# H0AR4_Backend.net
KiCad netlist of a schematic drawn in Altium Designer
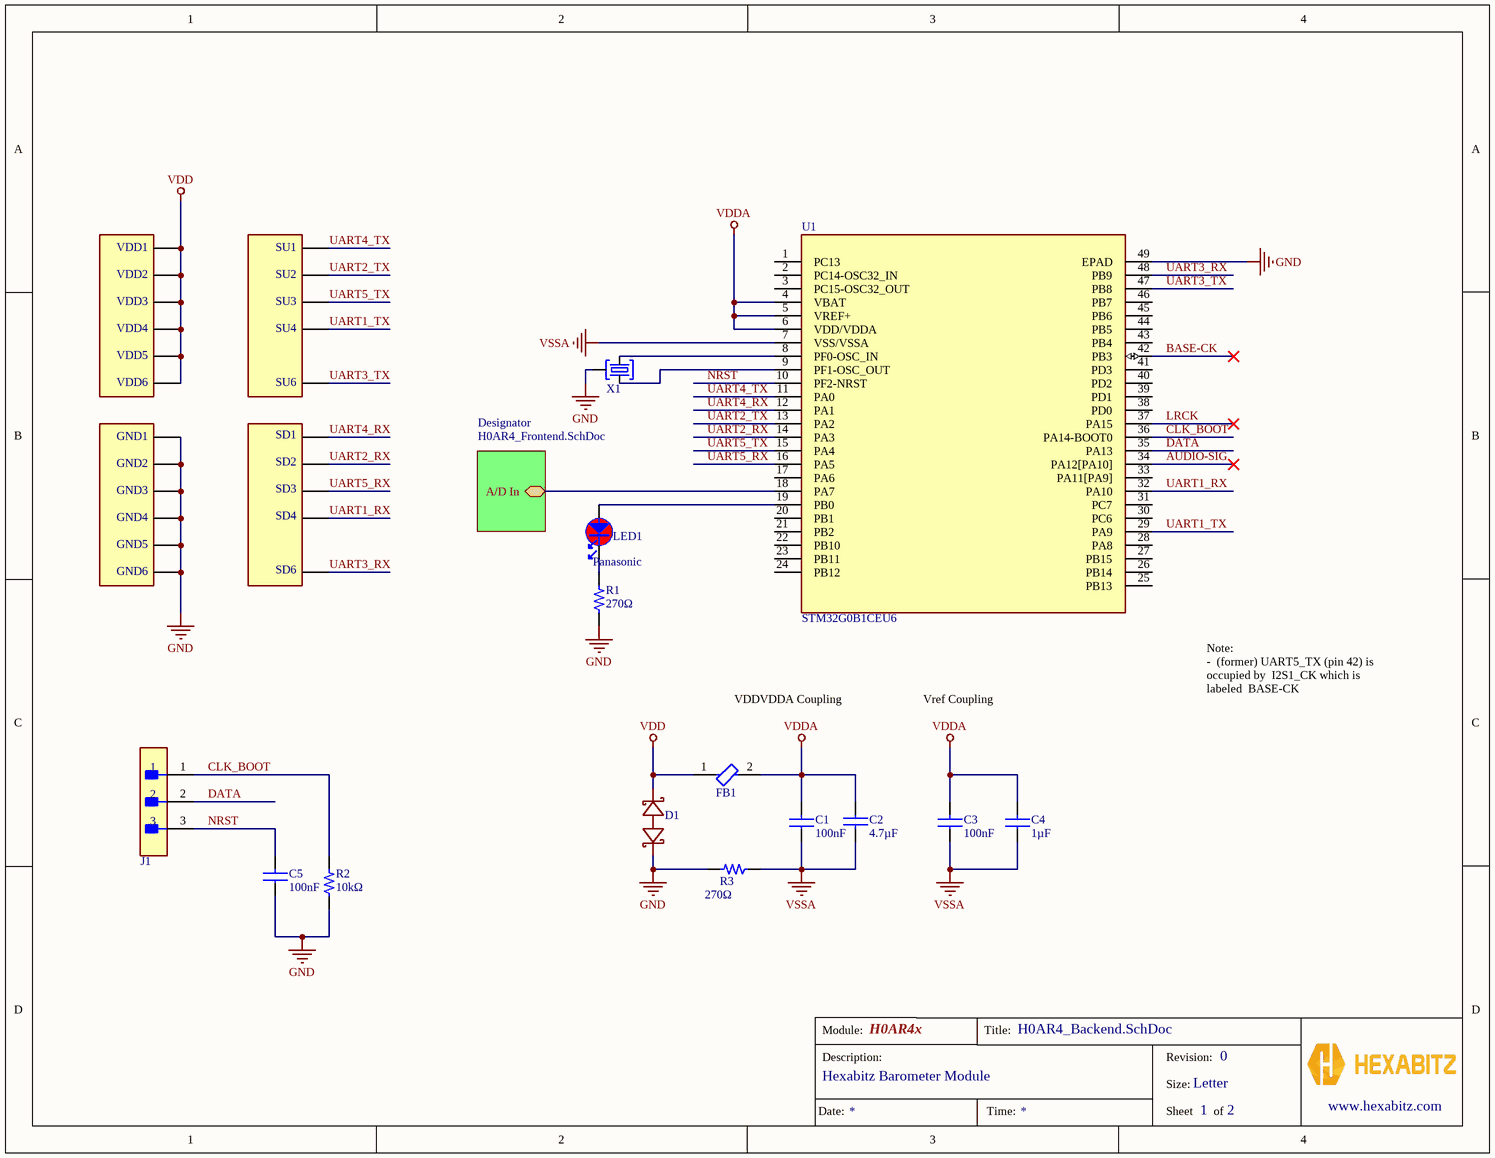
[diagram p0: H0AR4_Backend.SchDoc]

(export (version "E")
  (design (tool "Eeschema 10.0.6"))
  (components
    (comp (ref "C1")
      (value "100nF")
      (footprint "C0603")
      (fields
        (field (name "MANUFACTURER") "Samsung Electro-Mechanics")
        (field (name "MANUFACTURER PART NUMBER") "CL10B104KA8NNNC")
        (field (name "TOLERANCE") "10%")
      )
      (libsource (lib "Hexabitz Altium Library") (part "generic Capacitor"))
    )
    (comp (ref "C2")
      (value "4.7µF")
      (footprint "C0805")
      (fields
        (field (name "MANUFACTURER") "Samsung Electro-Mechanics")
        (field (name "MANUFACTURER PART NUMBER") "CL21X475KAQNNNE")
        (field (name "TOLERANCE") "10%")
      )
      (libsource (lib "Hexabitz Altium Library") (part "generic Capacitor"))
    )
    (comp (ref "C3")
      (value "100nF")
      (footprint "C0603")
      (fields
        (field (name "MANUFACTURER") "Samsung Electro-Mechanics")
        (field (name "MANUFACTURER PART NUMBER") "CL10B104KA8NNNC")
        (field (name "TOLERANCE") "10%")
      )
      (libsource (lib "Hexabitz Altium Library") (part "generic Capacitor"))
    )
    (comp (ref "C4")
      (value "1µF")
      (footprint "C0805")
      (description "Ceramic Capacitor, Ceramic, 16V, 10% +Tol, 10% -Tol, X7R, 15% TC, 1uF, Surface Mount, 0805")
      (fields
        (field (name "MANUFACTURER") "Yageo Group")
        (field (name "MANUFACTURER PART NUMBER") "CC0805KKX7R7BB105")
      )
      (libsource (lib "Hexabitz Altium Library") (part "generic Capacitor"))
    )
    (comp (ref "C5")
      (value "100nF")
      (footprint "C0603")
      (fields
        (field (name "MANUFACTURER") "Samsung Electro-Mechanics")
        (field (name "MANUFACTURER PART NUMBER") "CL10B104KA8NNNC")
        (field (name "TOLERANCE") "10%")
      )
      (libsource (lib "Hexabitz Altium Library") (part "generic Capacitor"))
    )
    (comp (ref "D1")
      (value "CDSOD323-T03SC")
      (footprint "SOD2513X114N")
      (description "A 3V, 350W, bi-directional, standard capacitance, SOD323 pkg TVS Diode ¦ Bourns CDSOD323-T03SC")
      (fields (field (name "MANUFACTURER") "Bourns"))
      (libsource (lib "Hexabitz Altium Library") (part "CDSOD323-T03SC"))
    )
    (comp (ref "FB1")
      (value "MMZ1608Y300B")
      (footprint "FP-MMZ1608-0_8-MFG")
      (description "Ferrite Beads 0603 30ohms 1500mA Signal Line AEC-Q200")
      (fields
        (field (name "MANUFACTURER") "TDK")
        (field (name "MANUFACTURER PART NUMBER") "MMZ1608Y300BTD25")
      )
      (libsource (lib "Hexabitz Altium Library") (part "MMZ1608Y300B"))
    )
    (comp (ref "GND1")
      (value "HEXABIT_UART_PORT")
      (footprint "HEXABIT_POWER_PORT_D")
      (libsource (lib "hexabitz_connectors.Library") (part "HEXABIT_POWER_PORT_D"))
    )
    (comp (ref "GND2")
      (value "HEXABIT_UART_PORT")
      (footprint "HEXABIT_POWER_PORT_D")
      (libsource (lib "hexabitz_connectors.Library") (part "HEXABIT_POWER_PORT_D"))
    )
    (comp (ref "GND3")
      (value "HEXABIT_UART_PORT")
      (footprint "HEXABIT_POWER_PORT_D")
      (libsource (lib "hexabitz_connectors.Library") (part "HEXABIT_POWER_PORT_D"))
    )
    (comp (ref "GND4")
      (value "HEXABIT_UART_PORT")
      (footprint "HEXABIT_POWER_PORT_D")
      (libsource (lib "hexabitz_connectors.Library") (part "HEXABIT_POWER_PORT_D"))
    )
    (comp (ref "GND5")
      (value "HEXABIT_UART_PORT")
      (footprint "HEXABIT_POWER_PORT_D")
      (libsource (lib "hexabitz_connectors.Library") (part "HEXABIT_POWER_PORT_D"))
    )
    (comp (ref "GND6")
      (value "HEXABIT_UART_PORT")
      (footprint "HEXABIT_POWER_PORT_D")
      (libsource (lib "hexabitz_connectors.Library") (part "HEXABIT_POWER_PORT_D"))
    )
    (comp (ref "J1")
      (value "TSW-103-14-G-S")
      (footprint "FP-TSW-103-14-G-S-MFG")
      (description "CONN HEADER VERT 3POS 2.54MM")
      (fields (field (name "MANUFACTURER") "Samtec"))
      (libsource (lib "Altium Content Vault") (part "cd3439d6ef35ae5d9b27ec4fdd3e828"))
    )
    (comp (ref "LED1")
      (value "VLMS1300-GS08")
      (footprint "FP-6_541-5092_01-4-MFG")
      (description "LED Uni-Color Super Red 639nm 2-Pin Chip 0603(1608Metric) T/R")
      (fields (field (name "MANUFACTURER") "Vishay Semiconductors"))
      (libsource (lib "Hexabitz Altium Library") (part "VLMS1300-GS08"))
    )
    (comp (ref "R1")
      (value "270Ω")
      (footprint "R0603")
      (description "Res Thick Film 0603 270 Ohm 5% 0.1W(1/10W) ±200ppm/C Pad SMD Automotive T/R")
      (fields
        (field (name "MANUFACTURER") "Panasonic")
        (field (name "MANUFACTURER PART NUMBER") "ERJ-3GEYJ271V")
        (field (name "TOLERANCE") "5%")
      )
      (libsource (lib "Hexabitz Altium Library") (part "generic Resistor"))
    )
    (comp (ref "R2")
      (value "10kΩ")
      (footprint "R0603")
      (description "100mW Thick Film Resistors ±100ppm/℃ ±1% 10kΩ 0603 Chip Resistor - Surface Mount ROHS")
      (fields
        (field (name "MANUFACTURER") "Yageo Group")
        (field (name "MANUFACTURER PART NUMBER") "RC0603FR-0710KL")
      )
      (libsource (lib "") (part "generic Resistor_1"))
    )
    (comp (ref "R3")
      (value "270Ω")
      (footprint "R0603")
      (description "Res Thick Film 0603 270 Ohm 5% 0.1W(1/10W) ±200ppm/C Pad SMD Automotive T/R")
      (fields (field (name "MANUFACTURER") "Panasonic") (field (name "Comment") "ERJ3GEYJ271V"))
      (libsource (lib "") (part "generic Resistor_2"))
    )
    (comp (ref "SD1")
      (value "HEXABIT_UART_PORT")
      (footprint "HEXABIT_UART_PORT_D")
      (libsource (lib "hexabitz_connectors.Library") (part "HEXABIT_UART_PORT_D"))
    )
    (comp (ref "SD2")
      (value "HEXABIT_UART_PORT")
      (footprint "HEXABIT_UART_PORT_D")
      (libsource (lib "hexabitz_connectors.Library") (part "HEXABIT_UART_PORT_D"))
    )
    (comp (ref "SD3")
      (value "HEXABIT_UART_PORT")
      (footprint "HEXABIT_UART_PORT_D")
      (libsource (lib "hexabitz_connectors.Library") (part "HEXABIT_UART_PORT_D"))
    )
    (comp (ref "SD4")
      (value "HEXABIT_UART_PORT")
      (footprint "HEXABIT_UART_PORT_D")
      (libsource (lib "hexabitz_connectors.Library") (part "HEXABIT_UART_PORT_D"))
    )
    (comp (ref "SD6")
      (value "HEXABIT_UART_PORT")
      (footprint "HEXABIT_UART_PORT_D")
      (libsource (lib "hexabitz_connectors.Library") (part "HEXABIT_UART_PORT_D"))
    )
    (comp (ref "SU1")
      (value "HEXABIT_UART_PORT")
      (footprint "HEXABIT_UART_PORT_U")
      (libsource (lib "hexabitz_connectors.Library") (part "HEXABIT_UART_PORT_U"))
    )
    (comp (ref "SU2")
      (value "HEXABIT_UART_PORT")
      (footprint "HEXABIT_UART_PORT_U")
      (libsource (lib "hexabitz_connectors.Library") (part "HEXABIT_UART_PORT_U"))
    )
    (comp (ref "SU3")
      (value "HEXABIT_UART_PORT")
      (footprint "HEXABIT_UART_PORT_U")
      (libsource (lib "hexabitz_connectors.Library") (part "HEXABIT_UART_PORT_U"))
    )
    (comp (ref "SU4")
      (value "HEXABIT_UART_PORT")
      (footprint "HEXABIT_UART_PORT_U")
      (libsource (lib "hexabitz_connectors.Library") (part "HEXABIT_UART_PORT_U"))
    )
    (comp (ref "SU6")
      (value "HEXABIT_UART_PORT")
      (footprint "HEXABIT_UART_PORT_U")
      (libsource (lib "hexabitz_connectors.Library") (part "HEXABIT_UART_PORT_U"))
    )
    (comp (ref "U1")
      (value "STM32G0B1CEU6")
      (footprint "QFN50P700X700X65-49N-D")
      (description "MCU 32-bit ARM Cortex M0+ RISC 512KB Flash 1.8V/2.5V/3.3V 48-Pin UFQFPN EP Tray")
      (fields
        (field (name "MANUFACTURER") "STMicroelectronics")
        (field (name "MANUFACTURER PART NUMBER") "STM32G0B1CEU6")
      )
      (libsource (lib "Hexabitz Altium Library") (part "STM32G0B1CEU6"))
    )
    (comp (ref "VDD1")
      (value "HEXABIT_UART_PORT")
      (footprint "HEXABIT_POWER_PORT_U")
      (libsource (lib "hexabitz_connectors.Library") (part "HEXABIT_POWER_PORT_U"))
    )
    (comp (ref "VDD2")
      (value "HEXABIT_UART_PORT")
      (footprint "HEXABIT_POWER_PORT_U")
      (libsource (lib "hexabitz_connectors.Library") (part "HEXABIT_POWER_PORT_U"))
    )
    (comp (ref "VDD3")
      (value "HEXABIT_UART_PORT")
      (footprint "HEXABIT_POWER_PORT_U")
      (libsource (lib "hexabitz_connectors.Library") (part "HEXABIT_POWER_PORT_U"))
    )
    (comp (ref "VDD4")
      (value "HEXABIT_UART_PORT")
      (footprint "HEXABIT_POWER_PORT_U")
      (libsource (lib "hexabitz_connectors.Library") (part "HEXABIT_POWER_PORT_U"))
    )
    (comp (ref "VDD5")
      (value "HEXABIT_UART_PORT")
      (footprint "HEXABIT_POWER_PORT_U")
      (libsource (lib "hexabitz_connectors.Library") (part "HEXABIT_POWER_PORT_U"))
    )
    (comp (ref "VDD6")
      (value "HEXABIT_UART_PORT")
      (footprint "HEXABIT_POWER_PORT_U")
      (libsource (lib "hexabitz_connectors.Library") (part "HEXABIT_POWER_PORT_U"))
    )
    (comp (ref "X1")
      (value "CSTCE8M00G52Z-R0")
      (footprint "XTALL_CSTCE8M00G52")
      (description "Ceramic Resonator 8MHz ±0.5% (Tol) ±0.2% (Stability) 10pF 40Ohm 3-Pin CSMD T/R")
      (fields (field (name "MANUFACTURER") "Murata") (field (name "TOLERANCE") "0.5%"))
      (libsource (lib "Hexabitz Altium Library") (part "CSTCE8M00G52Z-R0"))
    )
  )
  (nets
    (net (code "1") (name "/AUDIO-SIG") (class "Default")
      (node (ref "U1") (pin "34") (pinfunction "PA12[PA10]_34") (pintype "passive+no_connect"))
    )
    (net (code "2") (name "/A{slash}D In") (class "Default")
      (node (ref "U1") (pin "18") (pinfunction "PA7_18") (pintype "passive"))
    )
    (net (code "3") (name "/BASE-CK") (class "Default")
      (node (ref "U1") (pin "42") (pinfunction "PB3_42") (pintype "bidirectional+no_connect"))
    )
    (net (code "4") (name "/CLK_BOOT") (class "Default")
      (node (ref "J1") (pin "1") (pinfunction "1_1") (pintype "passive"))
      (node (ref "R2") (pin "1") (pinfunction "1_1") (pintype "passive"))
      (node (ref "U1") (pin "36") (pinfunction "PA14-BOOT0_36") (pintype "passive"))
    )
    (net (code "5") (name "/DATA") (class "Default")
      (node (ref "J1") (pin "2") (pinfunction "2_2") (pintype "passive"))
      (node (ref "U1") (pin "35") (pinfunction "PA13_35") (pintype "passive"))
    )
    (net (code "6") (name "/LRCK") (class "Default")
      (node (ref "U1") (pin "37") (pinfunction "PA15_37") (pintype "passive+no_connect"))
    )
    (net (code "7") (name "/NRST") (class "Default")
      (node (ref "C5") (pin "2") (pinfunction "2_2") (pintype "passive"))
      (node (ref "J1") (pin "3") (pinfunction "3_3") (pintype "passive"))
      (node (ref "U1") (pin "10") (pinfunction "PF2-NRST_10") (pintype "passive"))
    )
    (net (code "8") (name "/UART1_RX") (class "Default")
      (node (ref "SD4") (pin "UART_D") (pinfunction "UART_D_UART_D") (pintype "passive"))
      (node (ref "U1") (pin "32") (pinfunction "PA10_32") (pintype "passive"))
    )
    (net (code "9") (name "/UART1_TX") (class "Default")
      (node (ref "SU4") (pin "UART_U") (pinfunction "UART_U_UART_U") (pintype "passive"))
      (node (ref "U1") (pin "29") (pinfunction "PA9_29") (pintype "passive"))
    )
    (net (code "10") (name "/UART2_RX") (class "Default")
      (node (ref "SD2") (pin "UART_D") (pinfunction "UART_D_UART_D") (pintype "passive"))
      (node (ref "U1") (pin "14") (pinfunction "PA3_14") (pintype "passive"))
    )
    (net (code "11") (name "/UART2_TX") (class "Default")
      (node (ref "SU2") (pin "UART_U") (pinfunction "UART_U_UART_U") (pintype "passive"))
      (node (ref "U1") (pin "13") (pinfunction "PA2_13") (pintype "passive"))
    )
    (net (code "12") (name "/UART3_RX") (class "Default")
      (node (ref "SD6") (pin "UART_D") (pinfunction "UART_D_UART_D") (pintype "passive"))
      (node (ref "U1") (pin "48") (pinfunction "PB9_48") (pintype "passive"))
    )
    (net (code "13") (name "/UART3_TX") (class "Default")
      (node (ref "SU6") (pin "UART_U") (pinfunction "UART_U_UART_U") (pintype "passive"))
      (node (ref "U1") (pin "47") (pinfunction "PB8_47") (pintype "passive"))
    )
    (net (code "14") (name "/UART4_RX") (class "Default")
      (node (ref "SD1") (pin "UART_D") (pinfunction "UART_D_UART_D") (pintype "passive"))
      (node (ref "U1") (pin "12") (pinfunction "PA1_12") (pintype "passive"))
    )
    (net (code "15") (name "/UART4_TX") (class "Default")
      (node (ref "SU1") (pin "UART_U") (pinfunction "UART_U_UART_U") (pintype "passive"))
      (node (ref "U1") (pin "11") (pinfunction "PA0_11") (pintype "passive"))
    )
    (net (code "16") (name "/UART5_RX") (class "Default")
      (node (ref "SD3") (pin "UART_D") (pinfunction "UART_D_UART_D") (pintype "passive"))
      (node (ref "U1") (pin "16") (pinfunction "PA5_16") (pintype "passive"))
    )
    (net (code "17") (name "/UART5_TX") (class "Default")
      (node (ref "SU3") (pin "UART_U") (pinfunction "UART_U_UART_U") (pintype "passive"))
      (node (ref "U1") (pin "15") (pinfunction "PA4_15") (pintype "passive"))
    )
    (net (code "18") (name "GND") (class "Default")
      (node (ref "C5") (pin "1") (pinfunction "1_1") (pintype "passive"))
      (node (ref "D1") (pin "1") (pinfunction "A_1") (pintype "passive"))
      (node (ref "GND1") (pin "Pwr_D") (pinfunction "Pwr_D_Pwr_D") (pintype "passive"))
      (node (ref "GND2") (pin "Pwr_D") (pinfunction "Pwr_D_Pwr_D") (pintype "passive"))
      (node (ref "GND3") (pin "Pwr_D") (pinfunction "Pwr_D_Pwr_D") (pintype "passive"))
      (node (ref "GND4") (pin "Pwr_D") (pinfunction "Pwr_D_Pwr_D") (pintype "passive"))
      (node (ref "GND5") (pin "Pwr_D") (pinfunction "Pwr_D_Pwr_D") (pintype "passive"))
      (node (ref "GND6") (pin "Pwr_D") (pinfunction "Pwr_D_Pwr_D") (pintype "passive"))
      (node (ref "R1") (pin "1") (pinfunction "1_1") (pintype "passive"))
      (node (ref "R2") (pin "2") (pinfunction "2_2") (pintype "passive"))
      (node (ref "R3") (pin "1") (pinfunction "1_1") (pintype "passive"))
      (node (ref "U1") (pin "49") (pinfunction "EPAD_49") (pintype "passive"))
      (node (ref "X1") (pin "P$2") (pinfunction "2_P$2") (pintype "passive"))
    )
    (net (code "19") (name "Net-(LED1-Pad1)") (class "Default")
      (node (ref "LED1") (pin "1") (pintype "passive"))
      (node (ref "R1") (pin "2") (pinfunction "2_2") (pintype "passive"))
    )
    (net (code "20") (name "Net-(U1-PB0)") (class "Default")
      (node (ref "LED1") (pin "2") (pintype "passive"))
      (node (ref "U1") (pin "19") (pinfunction "PB0_19") (pintype "passive"))
    )
    (net (code "21") (name "Net-(U1-PF0-OSC_IN)") (class "Default")
      (node (ref "U1") (pin "8") (pinfunction "PF0-OSC_IN_8") (pintype "passive"))
      (node (ref "X1") (pin "P$3") (pinfunction "3_P$3") (pintype "passive"))
    )
    (net (code "22") (name "Net-(U1-PF1-OSC_OUT)") (class "Default")
      (node (ref "U1") (pin "9") (pinfunction "PF1-OSC_OUT_9") (pintype "passive"))
      (node (ref "X1") (pin "P$1") (pinfunction "1_P$1") (pintype "passive"))
    )
    (net (code "23") (name "VDD") (class "Default")
      (node (ref "D1") (pin "2") (pinfunction "C_2") (pintype "passive"))
      (node (ref "FB1") (pin "1") (pinfunction "1_1") (pintype "passive"))
      (node (ref "VDD1") (pin "Pwr_U") (pinfunction "Pwr_U_Pwr_U") (pintype "passive"))
      (node (ref "VDD2") (pin "Pwr_U") (pinfunction "Pwr_U_Pwr_U") (pintype "passive"))
      (node (ref "VDD3") (pin "Pwr_U") (pinfunction "Pwr_U_Pwr_U") (pintype "passive"))
      (node (ref "VDD4") (pin "Pwr_U") (pinfunction "Pwr_U_Pwr_U") (pintype "passive"))
      (node (ref "VDD5") (pin "Pwr_U") (pinfunction "Pwr_U_Pwr_U") (pintype "passive"))
      (node (ref "VDD6") (pin "Pwr_U") (pinfunction "Pwr_U_Pwr_U") (pintype "passive"))
    )
    (net (code "24") (name "VDDA") (class "Default")
      (node (ref "C1") (pin "2") (pinfunction "2_2") (pintype "passive"))
      (node (ref "C2") (pin "1") (pinfunction "1_1") (pintype "passive"))
      (node (ref "C3") (pin "2") (pinfunction "2_2") (pintype "passive"))
      (node (ref "C4") (pin "2") (pinfunction "2_2") (pintype "passive"))
      (node (ref "FB1") (pin "2") (pinfunction "2_2") (pintype "passive"))
      (node (ref "U1") (pin "4") (pinfunction "VBAT_4") (pintype "passive"))
      (node (ref "U1") (pin "5") (pinfunction "VREF+_5") (pintype "passive"))
      (node (ref "U1") (pin "6") (pinfunction "VDD/VDDA_6") (pintype "passive"))
    )
    (net (code "25") (name "VSSA") (class "Default")
      (node (ref "C1") (pin "1") (pinfunction "1_1") (pintype "passive"))
      (node (ref "C2") (pin "2") (pinfunction "2_2") (pintype "passive"))
      (node (ref "C3") (pin "1") (pinfunction "1_1") (pintype "passive"))
      (node (ref "C4") (pin "1") (pinfunction "1_1") (pintype "passive"))
      (node (ref "R3") (pin "2") (pinfunction "2_2") (pintype "passive"))
      (node (ref "U1") (pin "7") (pinfunction "VSS/VSSA_7") (pintype "passive"))
    )
    (net (code "26") (name "unconnected-(U1-PA6-Pad17)") (class "Default")
      (node (ref "U1") (pin "17") (pinfunction "PA6_17") (pintype "passive"))
    )
    (net (code "27") (name "unconnected-(U1-PA8-Pad28)") (class "Default")
      (node (ref "U1") (pin "28") (pinfunction "PA8_28") (pintype "passive"))
    )
    (net (code "28") (name "unconnected-(U1-PA11[PA9]-Pad33)") (class "Default")
      (node (ref "U1") (pin "33") (pinfunction "PA11[PA9]_33") (pintype "passive"))
    )
    (net (code "29") (name "unconnected-(U1-PB1-Pad20)") (class "Default")
      (node (ref "U1") (pin "20") (pinfunction "PB1_20") (pintype "passive"))
    )
    (net (code "30") (name "unconnected-(U1-PB2-Pad21)") (class "Default")
      (node (ref "U1") (pin "21") (pinfunction "PB2_21") (pintype "passive"))
    )
    (net (code "31") (name "unconnected-(U1-PB4-Pad43)") (class "Default")
      (node (ref "U1") (pin "43") (pinfunction "PB4_43") (pintype "passive"))
    )
    (net (code "32") (name "unconnected-(U1-PB5-Pad44)") (class "Default")
      (node (ref "U1") (pin "44") (pinfunction "PB5_44") (pintype "passive"))
    )
    (net (code "33") (name "unconnected-(U1-PB6-Pad45)") (class "Default")
      (node (ref "U1") (pin "45") (pinfunction "PB6_45") (pintype "passive"))
    )
    (net (code "34") (name "unconnected-(U1-PB7-Pad46)") (class "Default")
      (node (ref "U1") (pin "46") (pinfunction "PB7_46") (pintype "passive"))
    )
    (net (code "35") (name "unconnected-(U1-PB10-Pad22)") (class "Default")
      (node (ref "U1") (pin "22") (pinfunction "PB10_22") (pintype "passive"))
    )
    (net (code "36") (name "unconnected-(U1-PB11-Pad23)") (class "Default")
      (node (ref "U1") (pin "23") (pinfunction "PB11_23") (pintype "passive"))
    )
    (net (code "37") (name "unconnected-(U1-PB12-Pad24)") (class "Default")
      (node (ref "U1") (pin "24") (pinfunction "PB12_24") (pintype "passive"))
    )
    (net (code "38") (name "unconnected-(U1-PB13-Pad25)") (class "Default")
      (node (ref "U1") (pin "25") (pinfunction "PB13_25") (pintype "passive"))
    )
    (net (code "39") (name "unconnected-(U1-PB14-Pad26)") (class "Default")
      (node (ref "U1") (pin "26") (pinfunction "PB14_26") (pintype "passive"))
    )
    (net (code "40") (name "unconnected-(U1-PB15-Pad27)") (class "Default")
      (node (ref "U1") (pin "27") (pinfunction "PB15_27") (pintype "passive"))
    )
    (net (code "41") (name "unconnected-(U1-PC6-Pad30)") (class "Default")
      (node (ref "U1") (pin "30") (pinfunction "PC6_30") (pintype "passive"))
    )
    (net (code "42") (name "unconnected-(U1-PC7-Pad31)") (class "Default")
      (node (ref "U1") (pin "31") (pinfunction "PC7_31") (pintype "passive"))
    )
    (net (code "43") (name "unconnected-(U1-PC13-Pad1)") (class "Default")
      (node (ref "U1") (pin "1") (pinfunction "PC13_1") (pintype "passive"))
    )
    (net (code "44") (name "unconnected-(U1-PC14-OSC32_IN-Pad2)") (class "Default")
      (node (ref "U1") (pin "2") (pinfunction "PC14-OSC32_IN_2") (pintype "passive"))
    )
    (net (code "45") (name "unconnected-(U1-PC15-OSC32_OUT-Pad3)") (class "Default")
      (node (ref "U1") (pin "3") (pinfunction "PC15-OSC32_OUT_3") (pintype "passive"))
    )
    (net (code "46") (name "unconnected-(U1-PD0-Pad38)") (class "Default")
      (node (ref "U1") (pin "38") (pinfunction "PD0_38") (pintype "passive"))
    )
    (net (code "47") (name "unconnected-(U1-PD1-Pad39)") (class "Default")
      (node (ref "U1") (pin "39") (pinfunction "PD1_39") (pintype "passive"))
    )
    (net (code "48") (name "unconnected-(U1-PD2-Pad40)") (class "Default")
      (node (ref "U1") (pin "40") (pinfunction "PD2_40") (pintype "passive"))
    )
    (net (code "49") (name "unconnected-(U1-PD3-Pad41)") (class "Default")
      (node (ref "U1") (pin "41") (pinfunction "PD3_41") (pintype "passive"))
    )
  )
)
